# SMC_FrontPanel_ExtensionBoard_Step2_V14_.net
KiCad netlist of a schematic drawn in EAGLE
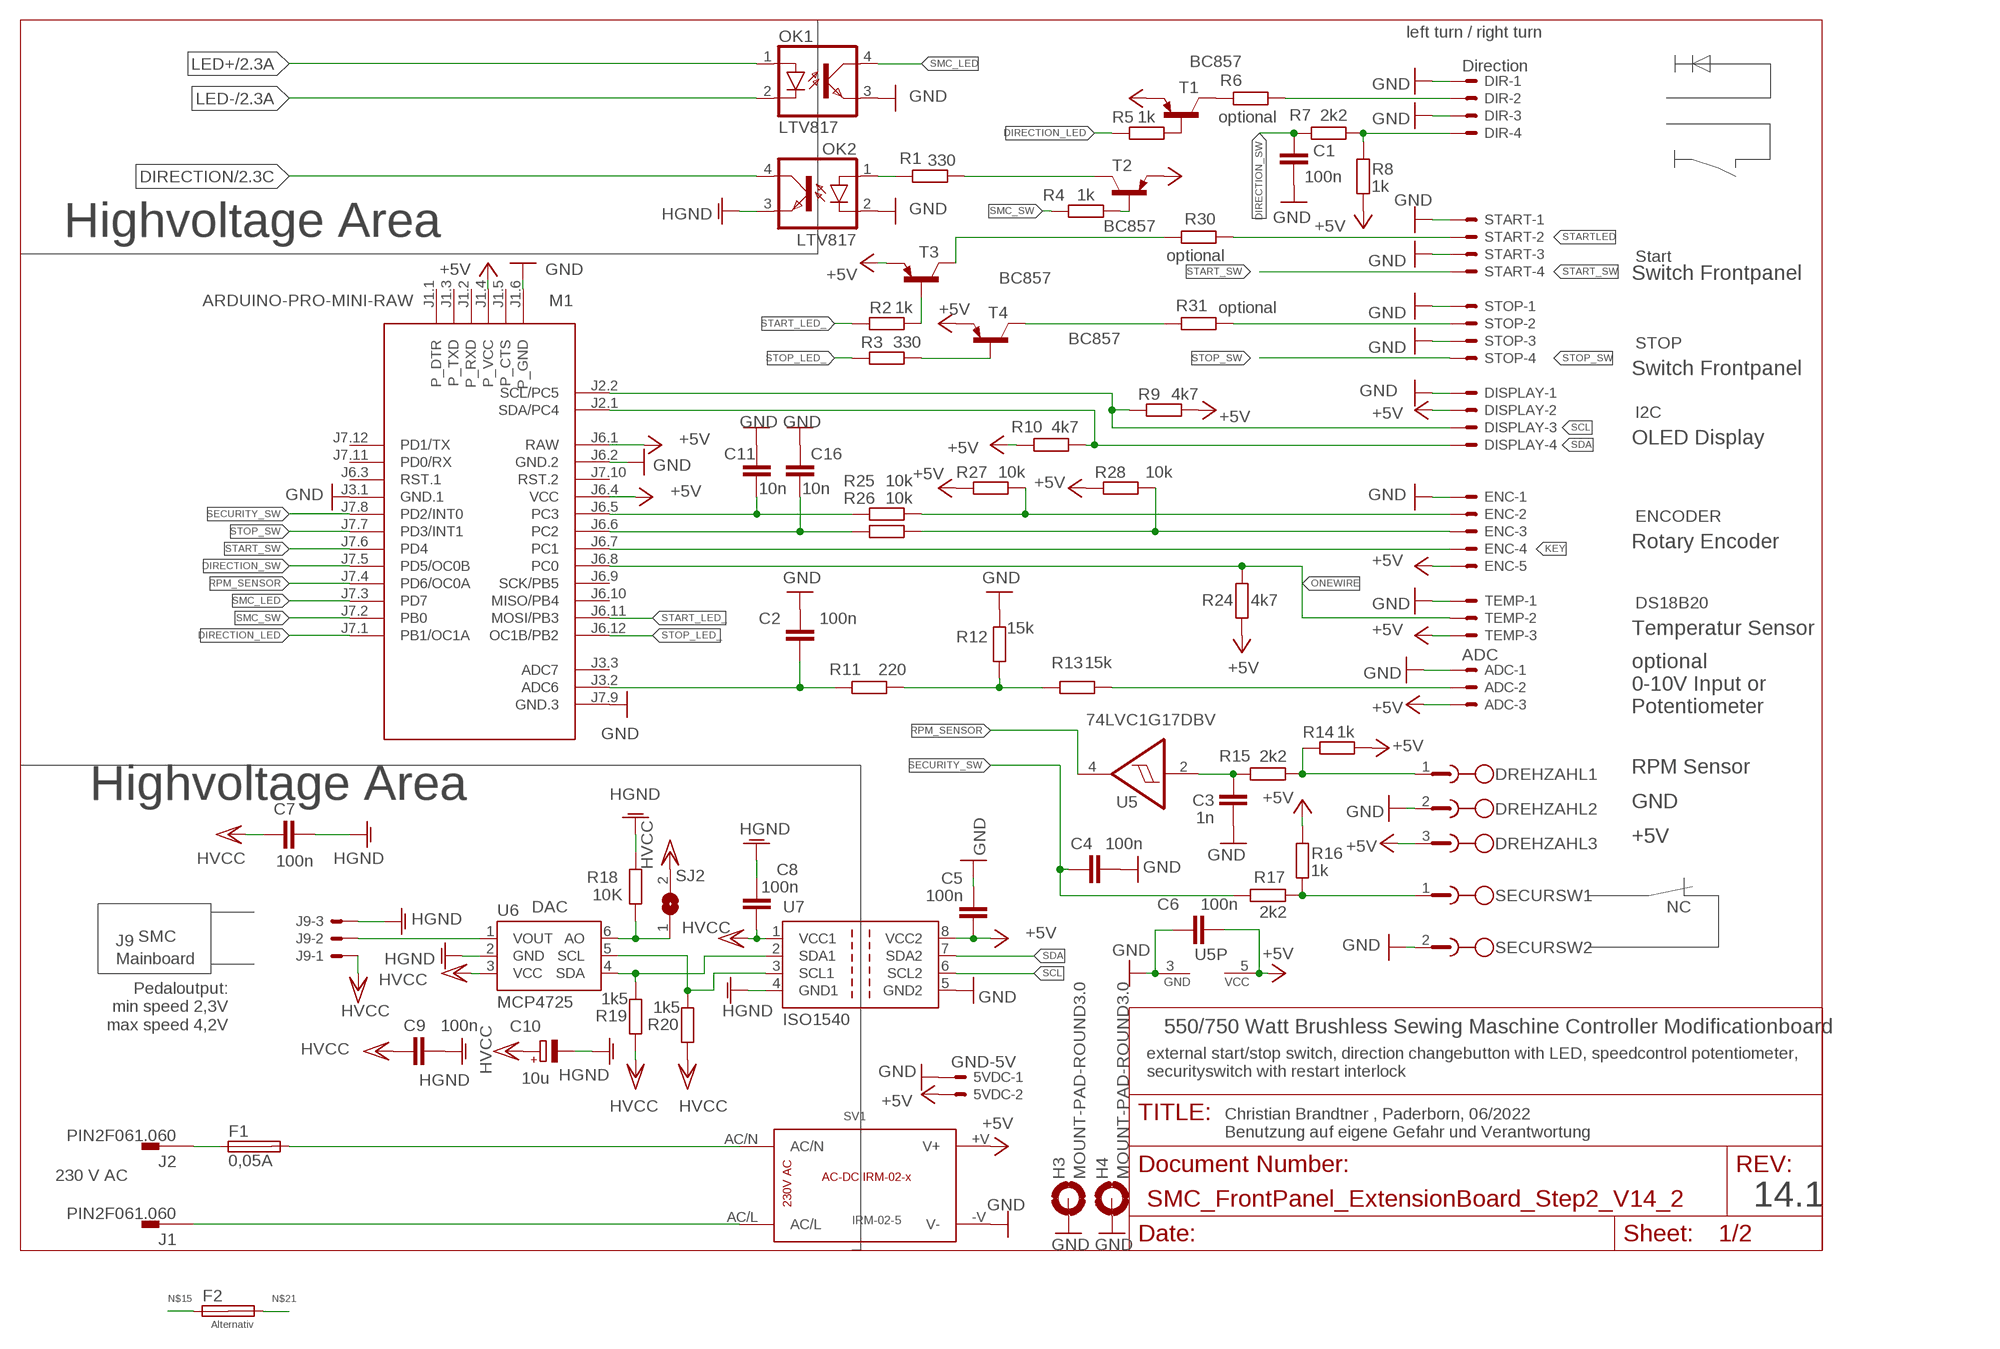
[diagram p0: schematic, sheet 1]
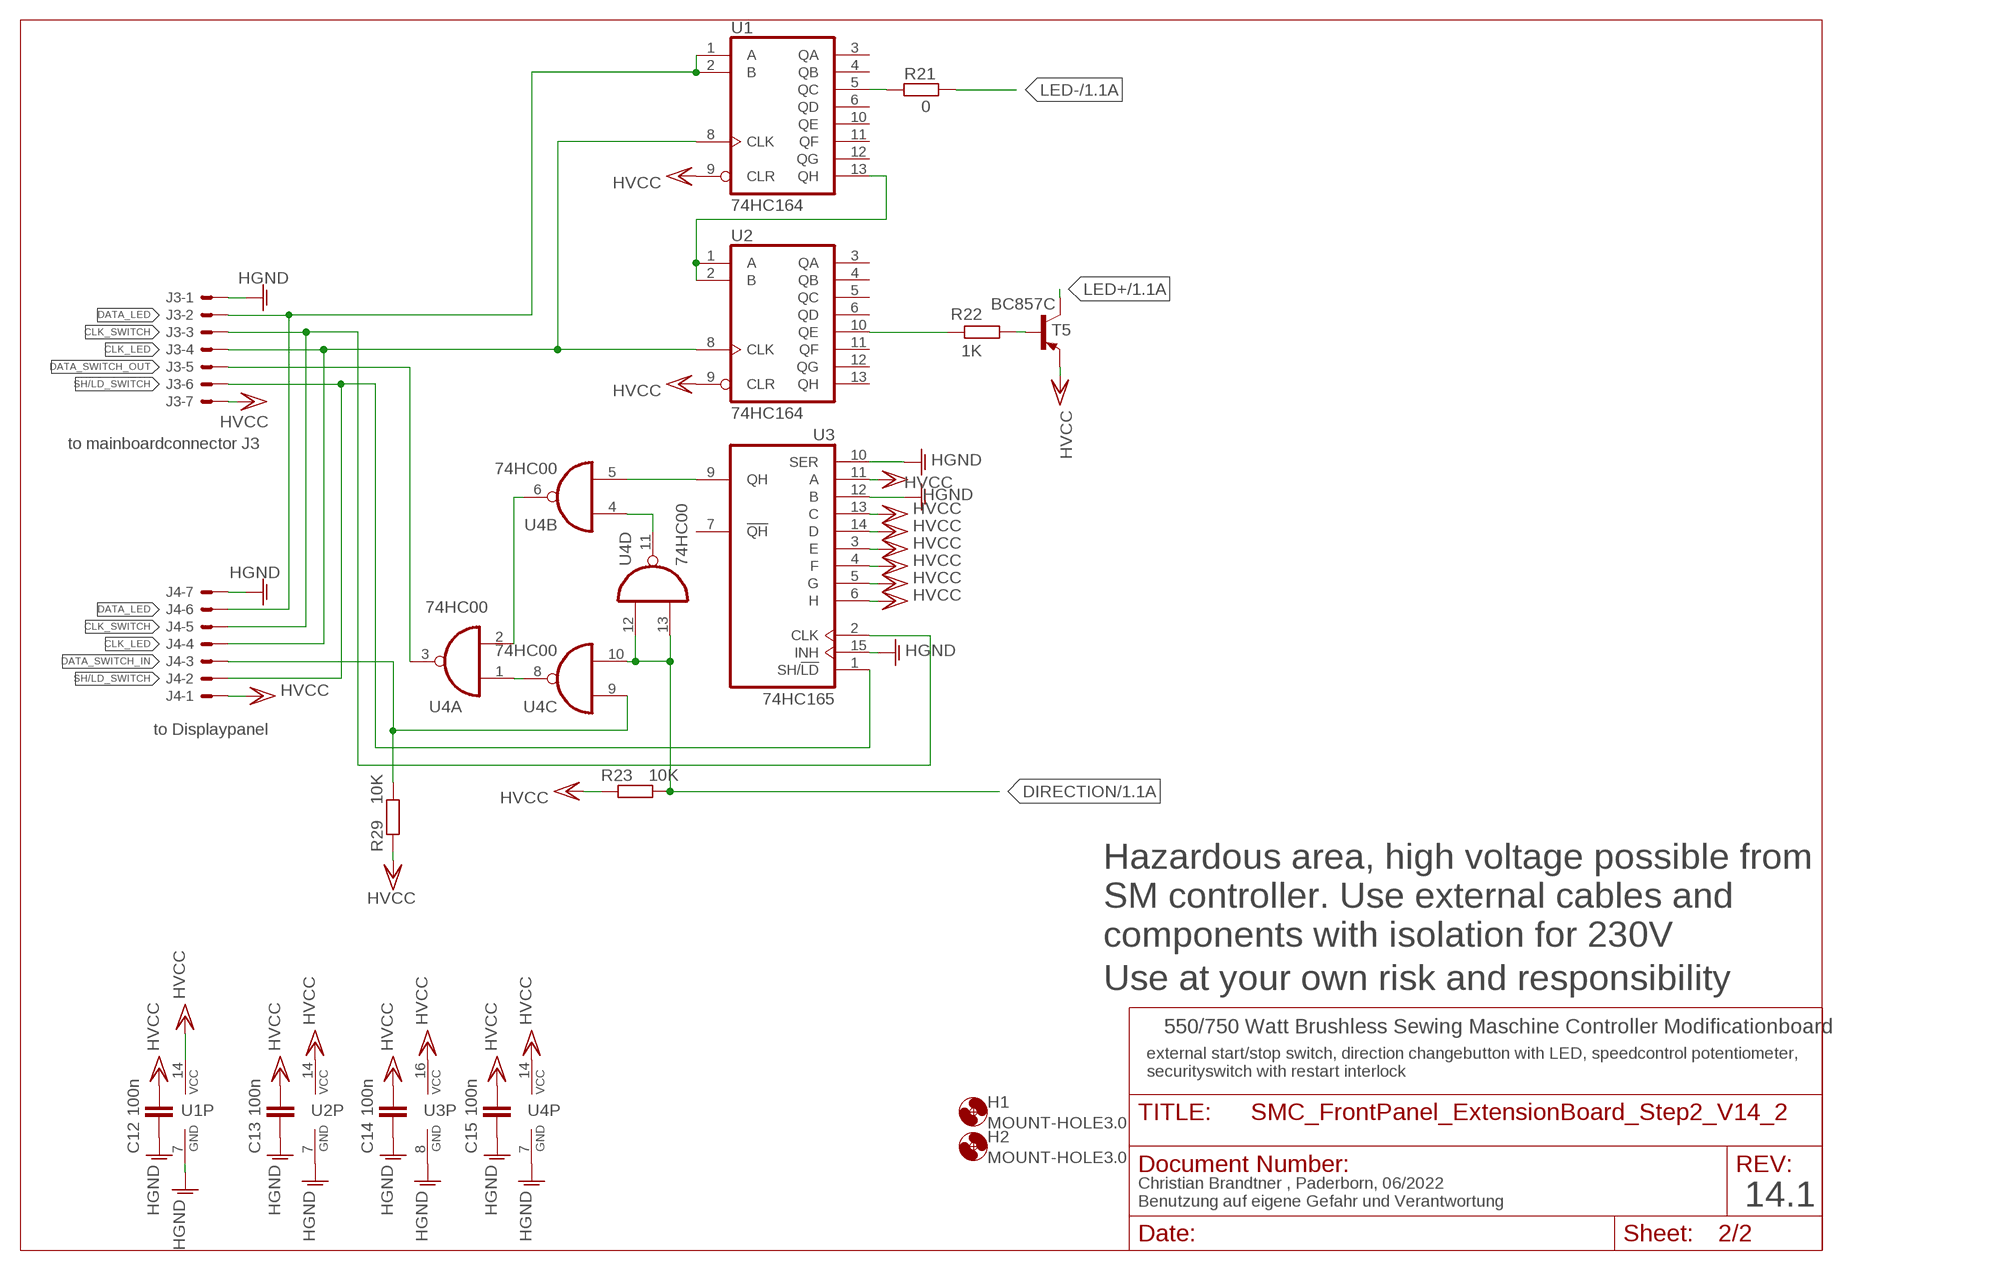
[diagram p1: schematic, sheet 2]

(export (version "E")
  (design (tool "Eeschema 10.0.6"))
  (components
    (comp (ref "C12")
      (value "100n")
      (footprint "eagle-import:C0805")
      (libsource (lib "eagle-import") (part "C-EUC0805"))
    )
    (comp (ref "C13")
      (value "100n")
      (footprint "eagle-import:C0805")
      (libsource (lib "eagle-import") (part "C-EUC0805"))
    )
    (comp (ref "C14")
      (value "100n")
      (footprint "eagle-import:C0805")
      (libsource (lib "eagle-import") (part "C-EUC0805"))
    )
    (comp (ref "C15")
      (value "100n")
      (footprint "eagle-import:C0805")
      (libsource (lib "eagle-import") (part "C-EUC0805"))
    )
    (comp (ref "H1")
      (value "MOUNT-HOLE3.0")
      (footprint "eagle-import:3,0")
      (libsource (lib "eagle-import") (part "MOUNT-HOLE3.0"))
    )
    (comp (ref "H2")
      (value "MOUNT-HOLE3.0")
      (footprint "eagle-import:3,0")
      (libsource (lib "eagle-import") (part "MOUNT-HOLE3.0"))
    )
    (comp (ref "J3")
      (value "to mainboardconnector J3")
      (footprint "eagle-import:JST-XH-07-PACKAGE-ROUND-PAD")
      (libsource (lib "eagle-import") (part "JST-XH-07-PIN-ROUND-PAD"))
    )
    (comp (ref "J4")
      (value "to Displaypanel")
      (footprint "eagle-import:JST-XH-07-PACKAGE-ROUND-PAD")
      (libsource (lib "eagle-import") (part "JST-XH-07-PIN-ROUND-PAD"))
    )
    (comp (ref "R21")
      (value "0")
      (footprint "eagle-import:R0805")
      (libsource (lib "eagle-import") (part "R-EU_R0805"))
    )
    (comp (ref "R22")
      (value "1K")
      (footprint "eagle-import:R0805")
      (libsource (lib "eagle-import") (part "R-EU_R0805"))
    )
    (comp (ref "R23")
      (value "10K")
      (footprint "eagle-import:R0805")
      (libsource (lib "eagle-import") (part "R-EU_R0805"))
    )
    (comp (ref "R29")
      (value "10K")
      (footprint "eagle-import:R0805")
      (libsource (lib "eagle-import") (part "R-EU_R0805"))
    )
    (comp (ref "T5")
      (value "BC857C")
      (footprint "eagle-import:SOT23-BEC")
      (libsource (lib "eagle-import") (part "-PNP-SOT23-BECBC857C"))
    )
    (comp (ref "U1")
      (value "74HC164")
      (footprint "eagle-import:SO14")
      (libsource (lib "eagle-import") (part "74164DHC"))
    )
    (comp (ref "U2")
      (value "74HC164")
      (footprint "eagle-import:SO14")
      (libsource (lib "eagle-import") (part "74164DHC"))
    )
    (comp (ref "U3")
      (value "74HC165")
      (footprint "eagle-import:SO16")
      (libsource (lib "eagle-import") (part "74165DHC"))
    )
    (comp (ref "U4")
      (value "74HC00")
      (footprint "eagle-import:SO14")
      (libsource (lib "eagle-import") (part "7400DHC"))
    )
    (comp (ref "5VDC")
      (value "GND-5V")
      (footprint "eagle-import:JST-XH-02-PACKAGE-ROUND-PAD")
      (libsource (lib "eagle-import") (part "JST-XH-02-PIN-ROUND-PAD"))
    )
    (comp (ref "ADC")
      (value "ADC")
      (footprint "eagle-import:JST-XH-03-PACKAGE-ROUND-PAD")
      (libsource (lib "eagle-import") (part "JST-XH-03-PIN-ROUND-PAD"))
    )
    (comp (ref "C1")
      (value "100n")
      (footprint "eagle-import:C0805")
      (libsource (lib "eagle-import") (part "C-EUC0805"))
    )
    (comp (ref "C2")
      (value "100n")
      (footprint "eagle-import:C0805")
      (libsource (lib "eagle-import") (part "C-EUC0805"))
    )
    (comp (ref "C3")
      (value "1n")
      (footprint "eagle-import:C0805")
      (libsource (lib "eagle-import") (part "C-EUC0805"))
    )
    (comp (ref "C4")
      (value "100n")
      (footprint "eagle-import:C0805")
      (libsource (lib "eagle-import") (part "C-EUC0805"))
    )
    (comp (ref "C5")
      (value "100n")
      (footprint "eagle-import:C0805")
      (libsource (lib "eagle-import") (part "C-EUC0805"))
    )
    (comp (ref "C6")
      (value "100n")
      (footprint "eagle-import:C0805")
      (libsource (lib "eagle-import") (part "C-EUC0805"))
    )
    (comp (ref "C7")
      (value "100n")
      (footprint "eagle-import:C0805")
      (libsource (lib "eagle-import") (part "C-EUC0805"))
    )
    (comp (ref "C8")
      (value "100n")
      (footprint "eagle-import:C0805")
      (libsource (lib "eagle-import") (part "C-EUC0805"))
    )
    (comp (ref "C9")
      (value "100n")
      (footprint "eagle-import:C0805")
      (libsource (lib "eagle-import") (part "C-EUC0805"))
    )
    (comp (ref "C10")
      (value "10u")
      (footprint "eagle-import:153CLV-0405")
      (libsource (lib "eagle-import") (part "CPOL-EU153CLV-0405"))
    )
    (comp (ref "C11")
      (value "10n")
      (footprint "eagle-import:C0805")
      (libsource (lib "eagle-import") (part "C-EUC0805"))
    )
    (comp (ref "C16")
      (value "10n")
      (footprint "eagle-import:C0805")
      (libsource (lib "eagle-import") (part "C-EUC0805"))
    )
    (comp (ref "DIR")
      (value "Direction")
      (footprint "eagle-import:JST-XH-04-PACKAGE-ROUND-PAD")
      (libsource (lib "eagle-import") (part "JST-XH-04-PIN-ROUND-PAD"))
    )
    (comp (ref "DISPLAY")
      (value "I2C")
      (footprint "eagle-import:JST-XH-04-PACKAGE-ROUND-PAD")
      (libsource (lib "eagle-import") (part "JST-XH-04-PIN-ROUND-PAD"))
    )
    (comp (ref "DREHZAHL")
      (value "MCV_1.5/3/-G-3.5")
      (footprint "eagle-import:1843619")
      (libsource (lib "eagle-import") (part "MCV_1.5/3/-G-3.5"))
    )
    (comp (ref "ENC")
      (value "ENCODER")
      (footprint "eagle-import:JST-XH-05-PACKAGE-ROUND-PAD")
      (libsource (lib "eagle-import") (part "JST-XH-05-PIN-ROUND-PAD"))
    )
    (comp (ref "F1")
      (value "0,05A")
      (footprint "eagle-import:MTA501100")
      (libsource (lib "eagle-import") (part "FUSE"))
    )
    (comp (ref "F2")
      (value "SHK20L")
      (footprint "eagle-import:SHK20L")
      (libsource (lib "eagle-import") (part "SHK20L"))
    )
    (comp (ref "H3")
      (value "MOUNT-PAD-ROUND3.0")
      (footprint "eagle-import:3,0-PAD")
      (libsource (lib "eagle-import") (part "MOUNT-PAD-ROUND3.0"))
    )
    (comp (ref "H4")
      (value "MOUNT-PAD-ROUND3.0")
      (footprint "eagle-import:3,0-PAD")
      (libsource (lib "eagle-import") (part "MOUNT-PAD-ROUND3.0"))
    )
    (comp (ref "J1")
      (value "PIN2F061.060")
      (footprint "eagle-import:F061.060")
      (libsource (lib "eagle-import") (part "PIN2F061.060"))
    )
    (comp (ref "J2")
      (value "PIN2F061.060")
      (footprint "eagle-import:F061.060")
      (libsource (lib "eagle-import") (part "PIN2F061.060"))
    )
    (comp (ref "J9")
      (value "JST-XH-03-PIN-ROUND-PAD")
      (footprint "eagle-import:JST-XH-03-PACKAGE-ROUND-PAD")
      (libsource (lib "eagle-import") (part "JST-XH-03-PIN-ROUND-PAD"))
    )
    (comp (ref "M1")
      (value "ARDUINO-PRO-MINI-RAW")
      (footprint "eagle-import:ARDUINO-PRO-MINI")
      (libsource (lib "eagle-import") (part "ARDUINO-PRO-MINI-RAW"))
    )
    (comp (ref "OK1")
      (value "LTV817")
      (footprint "eagle-import:SMD4-7")
      (fields (field (name "MF") "VISHAY/TELEFUNKEN") (field (name "MPN") "SFH6186-2"))
      (libsource (lib "eagle-import") (part "SFH618?6-2"))
    )
    (comp (ref "OK2")
      (value "LTV817")
      (footprint "eagle-import:SMD4-7")
      (fields (field (name "MF") "VISHAY/TELEFUNKEN") (field (name "MPN") "SFH6186-2"))
      (libsource (lib "eagle-import") (part "SFH618?6-2"))
    )
    (comp (ref "R1")
      (value "330")
      (footprint "eagle-import:R0805")
      (libsource (lib "eagle-import") (part "R-EU_R0805"))
    )
    (comp (ref "R2")
      (value "1k")
      (footprint "eagle-import:R0805")
      (libsource (lib "eagle-import") (part "R-EU_R0805"))
    )
    (comp (ref "R3")
      (value "330")
      (footprint "eagle-import:R0805")
      (libsource (lib "eagle-import") (part "R-EU_R0805"))
    )
    (comp (ref "R4")
      (value "1k")
      (footprint "eagle-import:R0805")
      (libsource (lib "eagle-import") (part "R-EU_R0805"))
    )
    (comp (ref "R5")
      (value "1k")
      (footprint "eagle-import:R0805")
      (libsource (lib "eagle-import") (part "R-EU_R0805"))
    )
    (comp (ref "R6")
      (value "optional")
      (footprint "eagle-import:R0805")
      (libsource (lib "eagle-import") (part "R-EU_R0805"))
    )
    (comp (ref "R7")
      (value "2k2")
      (footprint "eagle-import:R0805")
      (libsource (lib "eagle-import") (part "R-EU_R0805"))
    )
    (comp (ref "R8")
      (value "1k")
      (footprint "eagle-import:R0805")
      (libsource (lib "eagle-import") (part "R-EU_R0805"))
    )
    (comp (ref "R9")
      (value "4k7")
      (footprint "eagle-import:R0805")
      (libsource (lib "eagle-import") (part "R-EU_R0805"))
    )
    (comp (ref "R10")
      (value "4k7")
      (footprint "eagle-import:R0805")
      (libsource (lib "eagle-import") (part "R-EU_R0805"))
    )
    (comp (ref "R11")
      (value "220")
      (footprint "eagle-import:R0805")
      (libsource (lib "eagle-import") (part "R-EU_R0805"))
    )
    (comp (ref "R12")
      (value "15k")
      (footprint "eagle-import:R0805")
      (libsource (lib "eagle-import") (part "R-EU_R0805"))
    )
    (comp (ref "R13")
      (value "15k")
      (footprint "eagle-import:R0805")
      (libsource (lib "eagle-import") (part "R-EU_R0805"))
    )
    (comp (ref "R14")
      (value "1k")
      (footprint "eagle-import:R0805")
      (libsource (lib "eagle-import") (part "R-EU_R0805"))
    )
    (comp (ref "R15")
      (value "2k2")
      (footprint "eagle-import:R0805")
      (libsource (lib "eagle-import") (part "R-EU_R0805"))
    )
    (comp (ref "R16")
      (value "1k")
      (footprint "eagle-import:R0805")
      (libsource (lib "eagle-import") (part "R-EU_R0805"))
    )
    (comp (ref "R17")
      (value "2k2")
      (footprint "eagle-import:R0805")
      (libsource (lib "eagle-import") (part "R-EU_R0805"))
    )
    (comp (ref "R18")
      (value "10K")
      (footprint "eagle-import:R0805")
      (libsource (lib "eagle-import") (part "R-EU_R0805"))
    )
    (comp (ref "R19")
      (value "1k5")
      (footprint "eagle-import:R0805")
      (libsource (lib "eagle-import") (part "R-EU_R0805"))
    )
    (comp (ref "R20")
      (value "1k5")
      (footprint "eagle-import:R0805")
      (libsource (lib "eagle-import") (part "R-EU_R0805"))
    )
    (comp (ref "R24")
      (value "4k7")
      (footprint "eagle-import:R0805")
      (libsource (lib "eagle-import") (part "R-EU_R0805"))
    )
    (comp (ref "R25")
      (value "10k")
      (footprint "eagle-import:R0805")
      (libsource (lib "eagle-import") (part "R-EU_R0805"))
    )
    (comp (ref "R26")
      (value "10k")
      (footprint "eagle-import:R0805")
      (libsource (lib "eagle-import") (part "R-EU_R0805"))
    )
    (comp (ref "R27")
      (value "10k")
      (footprint "eagle-import:R0805")
      (libsource (lib "eagle-import") (part "R-EU_R0805"))
    )
    (comp (ref "R28")
      (value "10k")
      (footprint "eagle-import:R0805")
      (libsource (lib "eagle-import") (part "R-EU_R0805"))
    )
    (comp (ref "R30")
      (value "optional")
      (footprint "eagle-import:R0805")
      (libsource (lib "eagle-import") (part "R-EU_R0805"))
    )
    (comp (ref "R31")
      (value "optional")
      (footprint "eagle-import:R0805")
      (libsource (lib "eagle-import") (part "R-EU_R0805"))
    )
    (comp (ref "SECURSW")
      (value "MCV_1,5/2-G-3,5")
      (footprint "eagle-import:1843606")
      (libsource (lib "eagle-import") (part "MCV_1,5/2-G-3,5"))
    )
    (comp (ref "SJ2") (value "SJ") (footprint "eagle-import:SJ") (libsource (lib "eagle-import") (part "SJ")))
    (comp (ref "START")
      (value "Start")
      (footprint "eagle-import:JST-XH-04-PACKAGE-ROUND-PAD")
      (libsource (lib "eagle-import") (part "JST-XH-04-PIN-ROUND-PAD"))
    )
    (comp (ref "STOP")
      (value "STOP")
      (footprint "eagle-import:JST-XH-04-PACKAGE-ROUND-PAD")
      (libsource (lib "eagle-import") (part "JST-XH-04-PIN-ROUND-PAD"))
    )
    (comp (ref "SV1")
      (value "IRM-02-5")
      (footprint "eagle-import:IRM-02-X")
      (libsource (lib "eagle-import") (part "IRM-02-X"))
    )
    (comp (ref "T1")
      (value "BC857")
      (footprint "eagle-import:SOT23-BEC")
      (libsource (lib "eagle-import") (part "BC857SMDA"))
    )
    (comp (ref "T2")
      (value "BC857")
      (footprint "eagle-import:SOT23-BEC")
      (libsource (lib "eagle-import") (part "BC857SMDA"))
    )
    (comp (ref "T3")
      (value "BC857")
      (footprint "eagle-import:SOT23-BEC")
      (libsource (lib "eagle-import") (part "BC857SMDA"))
    )
    (comp (ref "T4")
      (value "BC857")
      (footprint "eagle-import:SOT23-BEC")
      (libsource (lib "eagle-import") (part "BC857SMDA"))
    )
    (comp (ref "TEMP")
      (value "DS18B20")
      (footprint "eagle-import:JST-XH-03-PACKAGE-ROUND-PAD")
      (libsource (lib "eagle-import") (part "JST-XH-03-PIN-ROUND-PAD"))
    )
    (comp (ref "U5")
      (value "74LVC1G17DBV")
      (footprint "eagle-import:SOT23-5")
      (libsource (lib "eagle-import") (part "741G17DBVLVC"))
    )
    (comp (ref "U6")
      (value "MCP4725")
      (footprint "eagle-import:SOT23-6")
      (libsource (lib "eagle-import") (part "MCP4725SOT-23"))
    )
    (comp (ref "U7")
      (value "ISO1540")
      (footprint "eagle-import:SO-08")
      (libsource (lib "eagle-import") (part "ISO1540"))
    )
  )
  (nets
    (net (code "1") (name "+5V") (class "Default")
      (node (ref "5VDC") (pin "2") (pinfunction "S_2") (pintype "passive"))
      (node (ref "ADC") (pin "3") (pinfunction "S_3") (pintype "passive"))
      (node (ref "C5") (pin "1") (pinfunction "1_1") (pintype "passive"))
      (node (ref "C6") (pin "1") (pinfunction "1_1") (pintype "passive"))
      (node (ref "DISPLAY") (pin "2") (pinfunction "S_2") (pintype "passive"))
      (node (ref "DREHZAHL") (pin "3") (pinfunction "1_3") (pintype "passive"))
      (node (ref "ENC") (pin "5") (pinfunction "S_5") (pintype "passive"))
      (node (ref "M1") (pin "J1.4") (pinfunction "P_VCC_J1.4") (pintype "bidirectional"))
      (node (ref "M1") (pin "J6.1") (pinfunction "RAW_J6.1") (pintype "power_in"))
      (node (ref "M1") (pin "J6.4") (pinfunction "VCC_J6.4") (pintype "power_in"))
      (node (ref "R10") (pin "1") (pinfunction "1_1") (pintype "passive"))
      (node (ref "R14") (pin "1") (pinfunction "1_1") (pintype "passive"))
      (node (ref "R16") (pin "1") (pinfunction "1_1") (pintype "passive"))
      (node (ref "R24") (pin "2") (pinfunction "2_2") (pintype "passive"))
      (node (ref "R27") (pin "1") (pinfunction "1_1") (pintype "passive"))
      (node (ref "R28") (pin "1") (pinfunction "1_1") (pintype "passive"))
      (node (ref "R8") (pin "2") (pinfunction "2_2") (pintype "passive"))
      (node (ref "R9") (pin "1") (pinfunction "1_1") (pintype "passive"))
      (node (ref "SV1") (pin "+V") (pinfunction "V+_+V") (pintype "bidirectional"))
      (node (ref "T1") (pin "E") (pinfunction "E_E") (pintype "passive"))
      (node (ref "T2") (pin "E") (pinfunction "E_E") (pintype "passive"))
      (node (ref "T3") (pin "E") (pinfunction "E_E") (pintype "passive"))
      (node (ref "T4") (pin "E") (pinfunction "E_E") (pintype "passive"))
      (node (ref "TEMP") (pin "3") (pinfunction "S_3") (pintype "passive"))
      (node (ref "U5") (pin "5") (pinfunction "VCC_5") (pintype "power_in"))
      (node (ref "U7") (pin "8") (pinfunction "VCC2_8") (pintype "power_in"))
    )
    (net (code "2") (name "CLK_LED") (class "Default")
      (node (ref "J3") (pin "4") (pinfunction "S_4") (pintype "passive"))
      (node (ref "J4") (pin "4") (pinfunction "S_4") (pintype "passive"))
      (node (ref "U1") (pin "8") (pinfunction "CLK_8") (pintype "input"))
      (node (ref "U2") (pin "8") (pinfunction "CLK_8") (pintype "input"))
    )
    (net (code "3") (name "CLK_SWITCH") (class "Default")
      (node (ref "J3") (pin "3") (pinfunction "S_3") (pintype "passive"))
      (node (ref "J4") (pin "5") (pinfunction "S_5") (pintype "passive"))
      (node (ref "U3") (pin "2") (pinfunction "CLK_2") (pintype "input"))
    )
    (net (code "4") (name "DATA_LED") (class "Default")
      (node (ref "J3") (pin "2") (pinfunction "S_2") (pintype "passive"))
      (node (ref "J4") (pin "6") (pinfunction "S_6") (pintype "passive"))
      (node (ref "U1") (pin "1") (pinfunction "A_1") (pintype "input"))
      (node (ref "U1") (pin "2") (pinfunction "B_2") (pintype "input"))
    )
    (net (code "5") (name "DATA_SWITCH_IN") (class "Default")
      (node (ref "J4") (pin "3") (pinfunction "S_3") (pintype "passive"))
      (node (ref "R29") (pin "1") (pinfunction "1_1") (pintype "passive"))
      (node (ref "U4") (pin "9") (pinfunction "I0_9") (pintype "input"))
    )
    (net (code "6") (name "DATA_SWITCH_OUT") (class "Default")
      (node (ref "J3") (pin "5") (pinfunction "S_5") (pintype "passive"))
      (node (ref "U4") (pin "3") (pinfunction "O_3") (pintype "output"))
    )
    (net (code "7") (name "DIRECTION") (class "Default")
      (node (ref "OK2") (pin "4") (pinfunction "COL_4") (pintype "passive"))
      (node (ref "R23") (pin "1") (pinfunction "1_1") (pintype "passive"))
      (node (ref "U4") (pin "10") (pinfunction "I1_10") (pintype "input"))
      (node (ref "U4") (pin "12") (pinfunction "I0_12") (pintype "input"))
      (node (ref "U4") (pin "13") (pinfunction "I1_13") (pintype "input"))
    )
    (net (code "8") (name "DIRECTION_LED") (class "Default")
      (node (ref "M1") (pin "J7.1") (pinfunction "PB1/OC1A_J7.1") (pintype "bidirectional"))
      (node (ref "R5") (pin "2") (pinfunction "2_2") (pintype "passive"))
    )
    (net (code "9") (name "DIRECTION_SW") (class "Default")
      (node (ref "C1") (pin "2") (pinfunction "2_2") (pintype "passive"))
      (node (ref "M1") (pin "J7.5") (pinfunction "PD5/OC0B_J7.5") (pintype "bidirectional"))
      (node (ref "R7") (pin "1") (pinfunction "1_1") (pintype "passive"))
    )
    (net (code "10") (name "GND") (class "Default")
      (node (ref "5VDC") (pin "1") (pinfunction "S_1") (pintype "passive"))
      (node (ref "ADC") (pin "1") (pinfunction "S_1") (pintype "passive"))
      (node (ref "C1") (pin "1") (pinfunction "1_1") (pintype "passive"))
      (node (ref "C11") (pin "2") (pinfunction "2_2") (pintype "passive"))
      (node (ref "C16") (pin "2") (pinfunction "2_2") (pintype "passive"))
      (node (ref "C2") (pin "2") (pinfunction "2_2") (pintype "passive"))
      (node (ref "C3") (pin "1") (pinfunction "1_1") (pintype "passive"))
      (node (ref "C4") (pin "2") (pinfunction "2_2") (pintype "passive"))
      (node (ref "C5") (pin "2") (pinfunction "2_2") (pintype "passive"))
      (node (ref "C6") (pin "2") (pinfunction "2_2") (pintype "passive"))
      (node (ref "DIR") (pin "1") (pinfunction "S_1") (pintype "passive"))
      (node (ref "DIR") (pin "3") (pinfunction "S_3") (pintype "passive"))
      (node (ref "DISPLAY") (pin "1") (pinfunction "S_1") (pintype "passive"))
      (node (ref "DREHZAHL") (pin "2") (pinfunction "1_2") (pintype "passive"))
      (node (ref "ENC") (pin "1") (pinfunction "S_1") (pintype "passive"))
      (node (ref "H3") (pin "B3,0") (pinfunction "MOUNT_B3,0") (pintype "passive"))
      (node (ref "H4") (pin "B3,0") (pinfunction "MOUNT_B3,0") (pintype "passive"))
      (node (ref "M1") (pin "J1.6") (pinfunction "P_GND_J1.6") (pintype "bidirectional"))
      (node (ref "M1") (pin "J3.1") (pinfunction "GND.1_J3.1") (pintype "power_in"))
      (node (ref "M1") (pin "J6.2") (pinfunction "GND.2_J6.2") (pintype "power_in"))
      (node (ref "M1") (pin "J7.9") (pinfunction "GND.3_J7.9") (pintype "bidirectional"))
      (node (ref "OK1") (pin "3") (pinfunction "EMIT_3") (pintype "passive"))
      (node (ref "OK2") (pin "2") (pinfunction "C_2") (pintype "passive"))
      (node (ref "R12") (pin "2") (pinfunction "2_2") (pintype "passive"))
      (node (ref "SECURSW") (pin "2") (pinfunction "1_2") (pintype "passive"))
      (node (ref "START") (pin "1") (pinfunction "S_1") (pintype "passive"))
      (node (ref "START") (pin "3") (pinfunction "S_3") (pintype "passive"))
      (node (ref "STOP") (pin "1") (pinfunction "S_1") (pintype "passive"))
      (node (ref "STOP") (pin "3") (pinfunction "S_3") (pintype "passive"))
      (node (ref "SV1") (pin "-V") (pinfunction "V-_-V") (pintype "bidirectional"))
      (node (ref "TEMP") (pin "1") (pinfunction "S_1") (pintype "passive"))
      (node (ref "U5") (pin "3") (pinfunction "GND_3") (pintype "power_in"))
      (node (ref "U7") (pin "5") (pinfunction "GND2_5") (pintype "power_in"))
    )
    (net (code "11") (name "HGND") (class "Default")
      (node (ref "C10") (pin "-") (pinfunction "-_-") (pintype "passive"))
      (node (ref "C12") (pin "1") (pinfunction "1_1") (pintype "passive"))
      (node (ref "C13") (pin "1") (pinfunction "1_1") (pintype "passive"))
      (node (ref "C14") (pin "1") (pinfunction "1_1") (pintype "passive"))
      (node (ref "C15") (pin "1") (pinfunction "1_1") (pintype "passive"))
      (node (ref "C7") (pin "1") (pinfunction "1_1") (pintype "passive"))
      (node (ref "C8") (pin "2") (pinfunction "2_2") (pintype "passive"))
      (node (ref "C9") (pin "1") (pinfunction "1_1") (pintype "passive"))
      (node (ref "J3") (pin "1") (pinfunction "S_1") (pintype "passive"))
      (node (ref "J4") (pin "7") (pinfunction "S_7") (pintype "passive"))
      (node (ref "J9") (pin "3") (pinfunction "S_3") (pintype "passive"))
      (node (ref "OK2") (pin "3") (pinfunction "EMIT_3") (pintype "passive"))
      (node (ref "R18") (pin "1") (pinfunction "1_1") (pintype "passive"))
      (node (ref "U1") (pin "7") (pinfunction "GND_7") (pintype "power_in"))
      (node (ref "U2") (pin "7") (pinfunction "GND_7") (pintype "power_in"))
      (node (ref "U3") (pin "10") (pinfunction "SER_10") (pintype "input"))
      (node (ref "U3") (pin "12") (pinfunction "B_12") (pintype "input"))
      (node (ref "U3") (pin "15") (pinfunction "INH_15") (pintype "input"))
      (node (ref "U3") (pin "8") (pinfunction "GND_8") (pintype "power_in"))
      (node (ref "U4") (pin "7") (pinfunction "GND_7") (pintype "power_in"))
      (node (ref "U6") (pin "2") (pinfunction "GND_2") (pintype "bidirectional"))
      (node (ref "U7") (pin "4") (pinfunction "GND1_4") (pintype "power_in"))
    )
    (net (code "12") (name "HVCC") (class "Default")
      (node (ref "C10") (pin "+") (pinfunction "+_+") (pintype "passive"))
      (node (ref "C12") (pin "2") (pinfunction "2_2") (pintype "passive"))
      (node (ref "C13") (pin "2") (pinfunction "2_2") (pintype "passive"))
      (node (ref "C14") (pin "2") (pinfunction "2_2") (pintype "passive"))
      (node (ref "C15") (pin "2") (pinfunction "2_2") (pintype "passive"))
      (node (ref "C7") (pin "2") (pinfunction "2_2") (pintype "passive"))
      (node (ref "C8") (pin "1") (pinfunction "1_1") (pintype "passive"))
      (node (ref "C9") (pin "2") (pinfunction "2_2") (pintype "passive"))
      (node (ref "J3") (pin "7") (pinfunction "S_7") (pintype "passive"))
      (node (ref "J4") (pin "1") (pinfunction "S_1") (pintype "passive"))
      (node (ref "J9") (pin "1") (pinfunction "S_1") (pintype "passive"))
      (node (ref "R19") (pin "2") (pinfunction "2_2") (pintype "passive"))
      (node (ref "R20") (pin "2") (pinfunction "2_2") (pintype "passive"))
      (node (ref "R23") (pin "2") (pinfunction "2_2") (pintype "passive"))
      (node (ref "R29") (pin "2") (pinfunction "2_2") (pintype "passive"))
      (node (ref "SJ2") (pin "2") (pinfunction "2_2") (pintype "passive"))
      (node (ref "T5") (pin "E") (pinfunction "E_E") (pintype "passive"))
      (node (ref "U1") (pin "14") (pinfunction "VCC_14") (pintype "power_in"))
      (node (ref "U1") (pin "9") (pinfunction "CLR_9") (pintype "input"))
      (node (ref "U2") (pin "14") (pinfunction "VCC_14") (pintype "power_in"))
      (node (ref "U2") (pin "9") (pinfunction "CLR_9") (pintype "input"))
      (node (ref "U3") (pin "11") (pinfunction "A_11") (pintype "input"))
      (node (ref "U3") (pin "13") (pinfunction "C_13") (pintype "input"))
      (node (ref "U3") (pin "14") (pinfunction "D_14") (pintype "input"))
      (node (ref "U3") (pin "16") (pinfunction "VCC_16") (pintype "power_in"))
      (node (ref "U3") (pin "3") (pinfunction "E_3") (pintype "input"))
      (node (ref "U3") (pin "4") (pinfunction "F_4") (pintype "input"))
      (node (ref "U3") (pin "5") (pinfunction "G_5") (pintype "input"))
      (node (ref "U3") (pin "6") (pinfunction "H_6") (pintype "input"))
      (node (ref "U4") (pin "14") (pinfunction "VCC_14") (pintype "power_in"))
      (node (ref "U6") (pin "3") (pinfunction "VCC_3") (pintype "bidirectional"))
      (node (ref "U7") (pin "1") (pinfunction "VCC1_1") (pintype "power_in"))
    )
    (net (code "13") (name "KEY") (class "Default")
      (node (ref "ENC") (pin "4") (pinfunction "S_4") (pintype "passive"))
      (node (ref "M1") (pin "J6.7") (pinfunction "PC1_J6.7") (pintype "bidirectional"))
    )
    (net (code "14") (name "LED+") (class "Default")
      (node (ref "OK1") (pin "1") (pinfunction "A_1") (pintype "passive"))
      (node (ref "T5") (pin "C") (pinfunction "C_C") (pintype "passive"))
    )
    (net (code "15") (name "LED-") (class "Default")
      (node (ref "OK1") (pin "2") (pinfunction "C_2") (pintype "passive"))
      (node (ref "R21") (pin "2") (pinfunction "2_2") (pintype "passive"))
    )
    (net (code "16") (name "N$15") (class "Default")
      (node (ref "F1") (pin "1") (pinfunction "1_1") (pintype "passive"))
      (node (ref "F2") (pin "1A") (pinfunction "1A_1A") (pintype "passive"))
      (node (ref "J2") (pin "A1") (pinfunction "1_A1") (pintype "passive"))
      (node (ref "J2") (pin "A2") (pinfunction "1_A2") (pintype "passive"))
    )
    (net (code "17") (name "N$21") (class "Default")
      (node (ref "F1") (pin "2") (pinfunction "2_2") (pintype "passive"))
      (node (ref "F2") (pin "2A") (pinfunction "2A_2A") (pintype "passive"))
      (node (ref "SV1") (pin "AC/N") (pinfunction "AC/N_AC/N") (pintype "bidirectional"))
    )
    (net (code "18") (name "Net-(ADCB-S)") (class "Default")
      (node (ref "ADC") (pin "2") (pinfunction "S_2") (pintype "passive"))
      (node (ref "R13") (pin "1") (pinfunction "1_1") (pintype "passive"))
    )
    (net (code "19") (name "Net-(DIRB-S)") (class "Default")
      (node (ref "DIR") (pin "2") (pinfunction "S_2") (pintype "passive"))
      (node (ref "R6") (pin "1") (pinfunction "1_1") (pintype "passive"))
    )
    (net (code "20") (name "Net-(DIRD-S)") (class "Default")
      (node (ref "DIR") (pin "4") (pinfunction "S_4") (pintype "passive"))
      (node (ref "R7") (pin "2") (pinfunction "2_2") (pintype "passive"))
      (node (ref "R8") (pin "1") (pinfunction "1_1") (pintype "passive"))
    )
    (net (code "21") (name "Net-(DREHZAHL-Pad1)") (class "Default")
      (node (ref "DREHZAHL") (pin "1") (pinfunction "1_1") (pintype "passive"))
      (node (ref "R14") (pin "2") (pinfunction "2_2") (pintype "passive"))
      (node (ref "R15") (pin "2") (pinfunction "2_2") (pintype "passive"))
    )
    (net (code "22") (name "Net-(ENCB-S)") (class "Default")
      (node (ref "ENC") (pin "2") (pinfunction "S_2") (pintype "passive"))
      (node (ref "R25") (pin "2") (pinfunction "2_2") (pintype "passive"))
      (node (ref "R27") (pin "2") (pinfunction "2_2") (pintype "passive"))
    )
    (net (code "23") (name "Net-(ENCC-S)") (class "Default")
      (node (ref "ENC") (pin "3") (pinfunction "S_3") (pintype "passive"))
      (node (ref "R26") (pin "2") (pinfunction "2_2") (pintype "passive"))
      (node (ref "R28") (pin "2") (pinfunction "2_2") (pintype "passive"))
    )
    (net (code "24") (name "Net-(J1-1-PadA1)") (class "Default")
      (node (ref "J1") (pin "A1") (pinfunction "1_A1") (pintype "passive"))
      (node (ref "J1") (pin "A2") (pinfunction "1_A2") (pintype "passive"))
      (node (ref "SV1") (pin "AC/L") (pinfunction "AC/L_AC/L") (pintype "bidirectional"))
    )
    (net (code "25") (name "Net-(J9B-S)") (class "Default")
      (node (ref "J9") (pin "2") (pinfunction "S_2") (pintype "passive"))
      (node (ref "U6") (pin "1") (pinfunction "VOUT_1") (pintype "bidirectional"))
    )
    (net (code "26") (name "Net-(M1-ADC6)") (class "Default")
      (node (ref "C2") (pin "1") (pinfunction "1_1") (pintype "passive"))
      (node (ref "M1") (pin "J3.2") (pinfunction "ADC6_J3.2") (pintype "bidirectional"))
      (node (ref "R11") (pin "1") (pinfunction "1_1") (pintype "passive"))
    )
    (net (code "27") (name "Net-(M1-PC2)") (class "Default")
      (node (ref "C16") (pin "1") (pinfunction "1_1") (pintype "passive"))
      (node (ref "M1") (pin "J6.6") (pinfunction "PC2_J6.6") (pintype "bidirectional"))
      (node (ref "R26") (pin "1") (pinfunction "1_1") (pintype "passive"))
    )
    (net (code "28") (name "Net-(M1-PC3)") (class "Default")
      (node (ref "C11") (pin "1") (pinfunction "1_1") (pintype "passive"))
      (node (ref "M1") (pin "J6.5") (pinfunction "PC3_J6.5") (pintype "bidirectional"))
      (node (ref "R25") (pin "1") (pinfunction "1_1") (pintype "passive"))
    )
    (net (code "29") (name "Net-(OK2-A)") (class "Default")
      (node (ref "OK2") (pin "1") (pinfunction "A_1") (pintype "passive"))
      (node (ref "R1") (pin "2") (pinfunction "2_2") (pintype "passive"))
    )
    (net (code "30") (name "Net-(R1-Pad1)") (class "Default")
      (node (ref "R1") (pin "1") (pinfunction "1_1") (pintype "passive"))
      (node (ref "T2") (pin "C") (pinfunction "C_C") (pintype "passive"))
    )
    (net (code "31") (name "Net-(R2-Pad1)") (class "Default")
      (node (ref "R2") (pin "1") (pinfunction "1_1") (pintype "passive"))
      (node (ref "T3") (pin "B") (pinfunction "B_B") (pintype "passive"))
    )
    (net (code "32") (name "Net-(R3-Pad1)") (class "Default")
      (node (ref "R3") (pin "1") (pinfunction "1_1") (pintype "passive"))
      (node (ref "T4") (pin "B") (pinfunction "B_B") (pintype "passive"))
    )
    (net (code "33") (name "Net-(R4-Pad1)") (class "Default")
      (node (ref "R4") (pin "1") (pinfunction "1_1") (pintype "passive"))
      (node (ref "T2") (pin "B") (pinfunction "B_B") (pintype "passive"))
    )
    (net (code "34") (name "Net-(R5-Pad1)") (class "Default")
      (node (ref "R5") (pin "1") (pinfunction "1_1") (pintype "passive"))
      (node (ref "T1") (pin "B") (pinfunction "B_B") (pintype "passive"))
    )
    (net (code "35") (name "Net-(R6-Pad2)") (class "Default")
      (node (ref "R6") (pin "2") (pinfunction "2_2") (pintype "passive"))
      (node (ref "T1") (pin "C") (pinfunction "C_C") (pintype "passive"))
    )
    (net (code "36") (name "Net-(R11-Pad2)") (class "Default")
      (node (ref "R11") (pin "2") (pinfunction "2_2") (pintype "passive"))
      (node (ref "R12") (pin "1") (pinfunction "1_1") (pintype "passive"))
      (node (ref "R13") (pin "2") (pinfunction "2_2") (pintype "passive"))
    )
    (net (code "37") (name "Net-(R16-Pad2)") (class "Default")
      (node (ref "R16") (pin "2") (pinfunction "2_2") (pintype "passive"))
      (node (ref "R17") (pin "2") (pinfunction "2_2") (pintype "passive"))
      (node (ref "SECURSW") (pin "1") (pinfunction "1_1") (pintype "passive"))
    )
    (net (code "38") (name "Net-(R22-Pad1)") (class "Default")
      (node (ref "R22") (pin "1") (pinfunction "1_1") (pintype "passive"))
      (node (ref "T5") (pin "B") (pinfunction "B_B") (pintype "passive"))
    )
    (net (code "39") (name "Net-(R31-Pad2)") (class "Default")
      (node (ref "R31") (pin "2") (pinfunction "2_2") (pintype "passive"))
      (node (ref "T4") (pin "C") (pinfunction "C_C") (pintype "passive"))
    )
    (net (code "40") (name "Net-(STARTB-S)") (class "Default")
      (node (ref "R30") (pin "1") (pinfunction "1_1") (pintype "passive"))
      (node (ref "START") (pin "2") (pinfunction "S_2") (pintype "passive"))
    )
    (net (code "41") (name "Net-(STOPB-S)") (class "Default")
      (node (ref "R31") (pin "1") (pinfunction "1_1") (pintype "passive"))
      (node (ref "STOP") (pin "2") (pinfunction "S_2") (pintype "passive"))
    )
    (net (code "42") (name "Net-(U1A-QC)") (class "Default")
      (node (ref "R21") (pin "1") (pinfunction "1_1") (pintype "passive"))
      (node (ref "U1") (pin "5") (pinfunction "QC_5") (pintype "output"))
    )
    (net (code "43") (name "Net-(U1A-QH)") (class "Default")
      (node (ref "U1") (pin "13") (pinfunction "QH_13") (pintype "output"))
      (node (ref "U2") (pin "1") (pinfunction "A_1") (pintype "input"))
      (node (ref "U2") (pin "2") (pinfunction "B_2") (pintype "input"))
    )
    (net (code "44") (name "Net-(U2A-QE)") (class "Default")
      (node (ref "R22") (pin "2") (pinfunction "2_2") (pintype "passive"))
      (node (ref "U2") (pin "10") (pinfunction "QE_10") (pintype "output"))
    )
    (net (code "45") (name "Net-(U3A-QH)") (class "Default")
      (node (ref "U3") (pin "9") (pinfunction "QH_9") (pintype "output"))
      (node (ref "U4") (pin "5") (pinfunction "I1_5") (pintype "input"))
    )
    (net (code "46") (name "Net-(U4A-I0)") (class "Default")
      (node (ref "U4") (pin "1") (pinfunction "I0_1") (pintype "input"))
      (node (ref "U4") (pin "8") (pinfunction "O_8") (pintype "output"))
    )
    (net (code "47") (name "Net-(U4A-I1)") (class "Default")
      (node (ref "U4") (pin "2") (pinfunction "I1_2") (pintype "input"))
      (node (ref "U4") (pin "6") (pinfunction "O_6") (pintype "output"))
    )
    (net (code "48") (name "Net-(U4B-I0)") (class "Default")
      (node (ref "U4") (pin "11") (pinfunction "O_11") (pintype "output"))
      (node (ref "U4") (pin "4") (pinfunction "I0_4") (pintype "input"))
    )
    (net (code "49") (name "Net-(U5A-I)") (class "Default")
      (node (ref "C3") (pin "2") (pinfunction "2_2") (pintype "passive"))
      (node (ref "R15") (pin "1") (pinfunction "1_1") (pintype "passive"))
      (node (ref "U5") (pin "2") (pinfunction "I_2") (pintype "input"))
    )
    (net (code "50") (name "Net-(U6-AO)") (class "Default")
      (node (ref "R18") (pin "2") (pinfunction "2_2") (pintype "passive"))
      (node (ref "SJ2") (pin "1") (pinfunction "1_1") (pintype "passive"))
      (node (ref "U6") (pin "6") (pinfunction "AO_6") (pintype "bidirectional"))
    )
    (net (code "51") (name "Net-(U6-SCL)") (class "Default")
      (node (ref "R20") (pin "1") (pinfunction "1_1") (pintype "passive"))
      (node (ref "U6") (pin "5") (pinfunction "SCL_5") (pintype "bidirectional"))
      (node (ref "U7") (pin "3") (pinfunction "SCL1_3") (pintype "input"))
    )
    (net (code "52") (name "Net-(U6-SDA)") (class "Default")
      (node (ref "R19") (pin "1") (pinfunction "1_1") (pintype "passive"))
      (node (ref "U6") (pin "4") (pinfunction "SDA_4") (pintype "bidirectional"))
      (node (ref "U7") (pin "2") (pinfunction "SDA1_2") (pintype "input"))
    )
    (net (code "53") (name "ONEWIRE") (class "Default")
      (node (ref "M1") (pin "J6.8") (pinfunction "PC0_J6.8") (pintype "bidirectional"))
      (node (ref "R24") (pin "1") (pinfunction "1_1") (pintype "passive"))
      (node (ref "TEMP") (pin "2") (pinfunction "S_2") (pintype "passive"))
    )
    (net (code "54") (name "RPM_SENSOR") (class "Default")
      (node (ref "M1") (pin "J7.4") (pinfunction "PD6/OC0A_J7.4") (pintype "bidirectional"))
      (node (ref "U5") (pin "4") (pinfunction "O_4") (pintype "output"))
    )
    (net (code "55") (name "SCL") (class "Default")
      (node (ref "DISPLAY") (pin "3") (pinfunction "S_3") (pintype "passive"))
      (node (ref "M1") (pin "J2.2") (pinfunction "SCL/PC5_J2.2") (pintype "bidirectional"))
      (node (ref "R9") (pin "2") (pinfunction "2_2") (pintype "passive"))
      (node (ref "U7") (pin "6") (pinfunction "SCL2_6") (pintype "output"))
    )
    (net (code "56") (name "SDA") (class "Default")
      (node (ref "DISPLAY") (pin "4") (pinfunction "S_4") (pintype "passive"))
      (node (ref "M1") (pin "J2.1") (pinfunction "SDA/PC4_J2.1") (pintype "bidirectional"))
      (node (ref "R10") (pin "2") (pinfunction "2_2") (pintype "passive"))
      (node (ref "U7") (pin "7") (pinfunction "SDA2_7") (pintype "output"))
    )
    (net (code "57") (name "SECURITY_SW") (class "Default")
      (node (ref "C4") (pin "1") (pinfunction "1_1") (pintype "passive"))
      (node (ref "M1") (pin "J7.8") (pinfunction "PD2/INT0_J7.8") (pintype "bidirectional"))
      (node (ref "R17") (pin "1") (pinfunction "1_1") (pintype "passive"))
    )
    (net (code "58") (name "SH{slash}LD_SWITCH") (class "Default")
      (node (ref "J3") (pin "6") (pinfunction "S_6") (pintype "passive"))
      (node (ref "J4") (pin "2") (pinfunction "S_2") (pintype "passive"))
      (node (ref "U3") (pin "1") (pinfunction "SH/~{LD}_1") (pintype "input"))
    )
    (net (code "59") (name "SMC_LED") (class "Default")
      (node (ref "M1") (pin "J7.3") (pinfunction "PD7_J7.3") (pintype "bidirectional"))
      (node (ref "OK1") (pin "4") (pinfunction "COL_4") (pintype "passive"))
    )
    (net (code "60") (name "SMC_SW") (class "Default")
      (node (ref "M1") (pin "J7.2") (pinfunction "PB0_J7.2") (pintype "bidirectional"))
      (node (ref "R4") (pin "2") (pinfunction "2_2") (pintype "passive"))
    )
    (net (code "61") (name "STARTLED") (class "Default")
      (node (ref "R30") (pin "2") (pinfunction "2_2") (pintype "passive"))
      (node (ref "T3") (pin "C") (pinfunction "C_C") (pintype "passive"))
    )
    (net (code "62") (name "START_LED_") (class "Default")
      (node (ref "M1") (pin "J6.11") (pinfunction "MOSI/PB3_J6.11") (pintype "bidirectional"))
      (node (ref "R2") (pin "2") (pinfunction "2_2") (pintype "passive"))
    )
    (net (code "63") (name "START_SW") (class "Default")
      (node (ref "M1") (pin "J7.6") (pinfunction "PD4_J7.6") (pintype "bidirectional"))
      (node (ref "START") (pin "4") (pinfunction "S_4") (pintype "passive"))
    )
    (net (code "64") (name "STOP_LED_") (class "Default")
      (node (ref "M1") (pin "J6.12") (pinfunction "OC1B/PB2_J6.12") (pintype "bidirectional"))
      (node (ref "R3") (pin "2") (pinfunction "2_2") (pintype "passive"))
    )
    (net (code "65") (name "STOP_SW") (class "Default")
      (node (ref "M1") (pin "J7.7") (pinfunction "PD3/INT1_J7.7") (pintype "bidirectional"))
      (node (ref "STOP") (pin "4") (pinfunction "S_4") (pintype "passive"))
    )
    (net (code "66") (name "unconnected-(F2-Pad1B)") (class "Default")
      (node (ref "F2") (pin "1B") (pinfunction "1B_1B") (pintype "passive"))
    )
    (net (code "67") (name "unconnected-(F2-Pad2B)") (class "Default")
      (node (ref "F2") (pin "2B") (pinfunction "2B_2B") (pintype "passive"))
    )
    (net (code "68") (name "unconnected-(M1-ADC7-PadJ3.3)") (class "Default")
      (node (ref "M1") (pin "J3.3") (pinfunction "ADC7_J3.3") (pintype "bidirectional"))
    )
    (net (code "69") (name "unconnected-(M1-MISO{slash}PB4-PadJ6.10)") (class "Default")
      (node (ref "M1") (pin "J6.10") (pinfunction "MISO/PB4_J6.10") (pintype "bidirectional"))
    )
    (net (code "70") (name "unconnected-(M1-PD0{slash}RX-PadJ7.11)") (class "Default")
      (node (ref "M1") (pin "J7.11") (pinfunction "PD0/RX_J7.11") (pintype "bidirectional"))
    )
    (net (code "71") (name "unconnected-(M1-PD1{slash}TX-PadJ7.12)") (class "Default")
      (node (ref "M1") (pin "J7.12") (pinfunction "PD1/TX_J7.12") (pintype "bidirectional"))
    )
    (net (code "72") (name "unconnected-(M1-P_CTS-PadJ1.5)") (class "Default")
      (node (ref "M1") (pin "J1.5") (pinfunction "P_CTS_J1.5") (pintype "bidirectional"))
    )
    (net (code "73") (name "unconnected-(M1-P_DTR-PadJ1.1)") (class "Default")
      (node (ref "M1") (pin "J1.1") (pinfunction "P_DTR_J1.1") (pintype "bidirectional"))
    )
    (net (code "74") (name "unconnected-(M1-P_RXD-PadJ1.2)") (class "Default")
      (node (ref "M1") (pin "J1.2") (pinfunction "P_RXD_J1.2") (pintype "bidirectional"))
    )
    (net (code "75") (name "unconnected-(M1-P_TXD-PadJ1.3)") (class "Default")
      (node (ref "M1") (pin "J1.3") (pinfunction "P_TXD_J1.3") (pintype "bidirectional"))
    )
    (net (code "76") (name "unconnected-(M1-RST.1-PadJ6.3)") (class "Default")
      (node (ref "M1") (pin "J6.3") (pinfunction "RST.1_J6.3") (pintype "bidirectional"))
    )
    (net (code "77") (name "unconnected-(M1-RST.2-PadJ7.10)") (class "Default")
      (node (ref "M1") (pin "J7.10") (pinfunction "RST.2_J7.10") (pintype "bidirectional"))
    )
    (net (code "78") (name "unconnected-(M1-SCK{slash}PB5-PadJ6.9)") (class "Default")
      (node (ref "M1") (pin "J6.9") (pinfunction "SCK/PB5_J6.9") (pintype "bidirectional"))
    )
    (net (code "79") (name "unconnected-(U1A-QA-Pad3)") (class "Default")
      (node (ref "U1") (pin "3") (pinfunction "QA_3") (pintype "output"))
    )
    (net (code "80") (name "unconnected-(U1A-QB-Pad4)") (class "Default")
      (node (ref "U1") (pin "4") (pinfunction "QB_4") (pintype "output"))
    )
    (net (code "81") (name "unconnected-(U1A-QD-Pad6)") (class "Default")
      (node (ref "U1") (pin "6") (pinfunction "QD_6") (pintype "output"))
    )
    (net (code "82") (name "unconnected-(U1A-QE-Pad10)") (class "Default")
      (node (ref "U1") (pin "10") (pinfunction "QE_10") (pintype "output"))
    )
    (net (code "83") (name "unconnected-(U1A-QF-Pad11)") (class "Default")
      (node (ref "U1") (pin "11") (pinfunction "QF_11") (pintype "output"))
    )
    (net (code "84") (name "unconnected-(U1A-QG-Pad12)") (class "Default")
      (node (ref "U1") (pin "12") (pinfunction "QG_12") (pintype "output"))
    )
    (net (code "85") (name "unconnected-(U2A-QA-Pad3)") (class "Default")
      (node (ref "U2") (pin "3") (pinfunction "QA_3") (pintype "output"))
    )
    (net (code "86") (name "unconnected-(U2A-QB-Pad4)") (class "Default")
      (node (ref "U2") (pin "4") (pinfunction "QB_4") (pintype "output"))
    )
    (net (code "87") (name "unconnected-(U2A-QC-Pad5)") (class "Default")
      (node (ref "U2") (pin "5") (pinfunction "QC_5") (pintype "output"))
    )
    (net (code "88") (name "unconnected-(U2A-QD-Pad6)") (class "Default")
      (node (ref "U2") (pin "6") (pinfunction "QD_6") (pintype "output"))
    )
    (net (code "89") (name "unconnected-(U2A-QF-Pad11)") (class "Default")
      (node (ref "U2") (pin "11") (pinfunction "QF_11") (pintype "output"))
    )
    (net (code "90") (name "unconnected-(U2A-QG-Pad12)") (class "Default")
      (node (ref "U2") (pin "12") (pinfunction "QG_12") (pintype "output"))
    )
    (net (code "91") (name "unconnected-(U2A-QH-Pad13)") (class "Default")
      (node (ref "U2") (pin "13") (pinfunction "QH_13") (pintype "output"))
    )
    (net (code "92") (name "unconnected-(U3A-~{QH}-Pad7)") (class "Default")
      (node (ref "U3") (pin "7") (pinfunction "~{QH}_7") (pintype "output"))
    )
  )
)
